# Controller_Keinz_2023.net
KiCad netlist of a schematic drawn in EAGLE
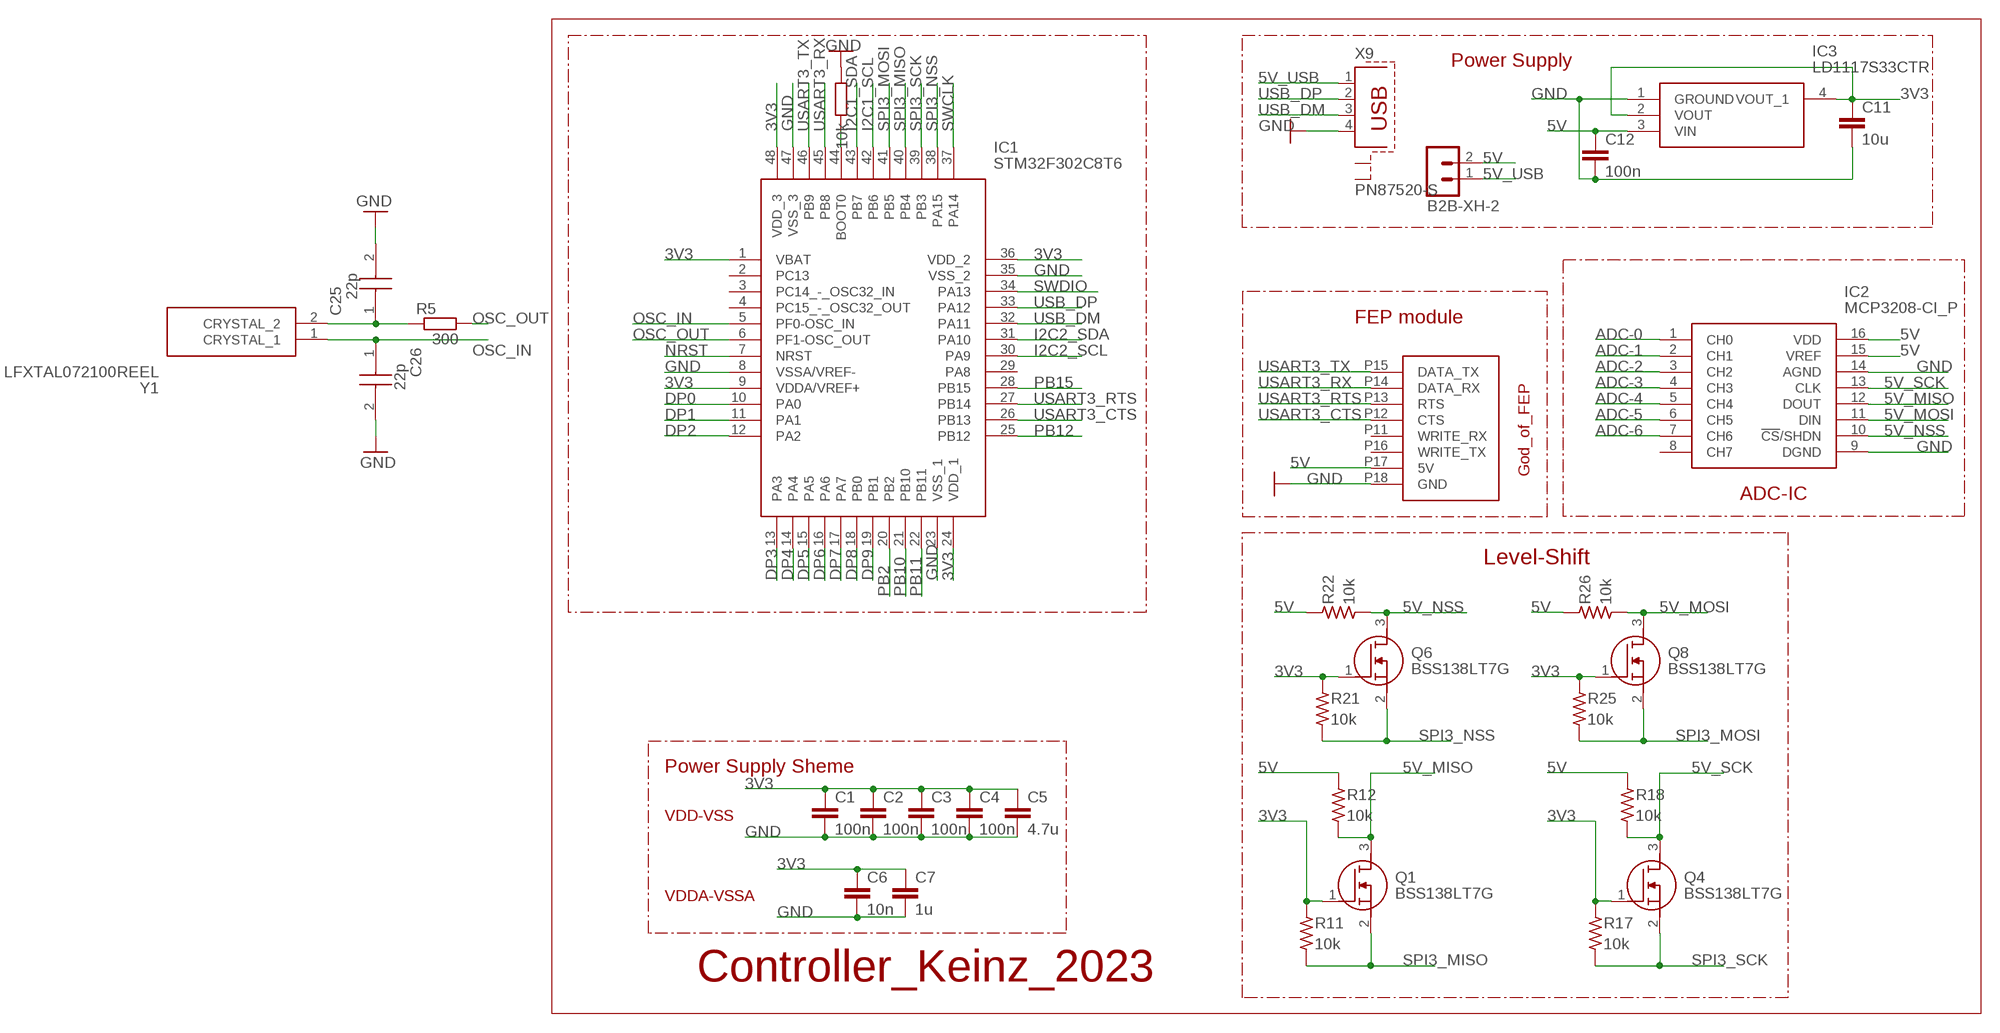
[diagram p0: schematic, sheet 1]
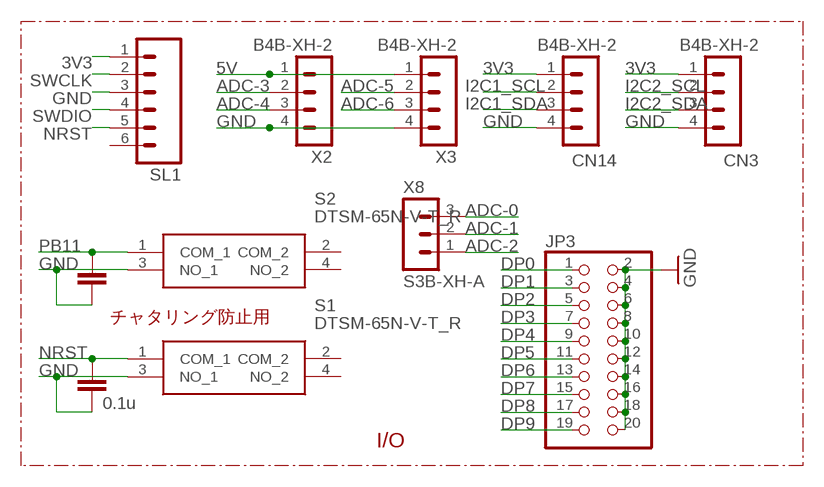
[diagram p1: schematic, sheet 2]
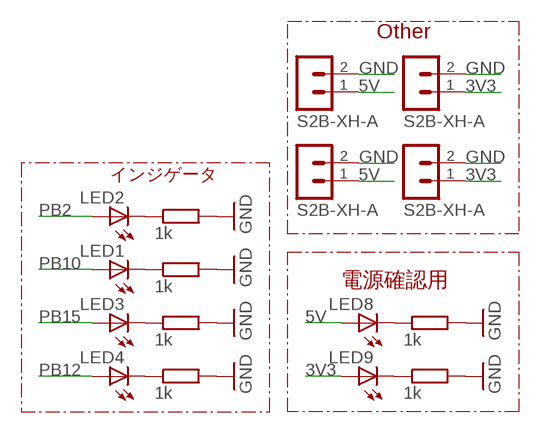
[diagram p2: schematic, sheet 3]

(export (version "E")
  (design (tool "Eeschema 10.0.6"))
  (components
    (comp (ref "LED1")
      (value "LEDCHIP-LED0805")
      (footprint "eagle-import:CHIP-LED0805")
      (libsource (lib "eagle-import") (part "LEDCHIP-LED0805"))
    )
    (comp (ref "LED2")
      (value "LEDCHIP-LED0805")
      (footprint "eagle-import:CHIP-LED0805")
      (libsource (lib "eagle-import") (part "LEDCHIP-LED0805"))
    )
    (comp (ref "LED3")
      (value "LEDCHIP-LED0805")
      (footprint "eagle-import:CHIP-LED0805")
      (libsource (lib "eagle-import") (part "LEDCHIP-LED0805"))
    )
    (comp (ref "LED4")
      (value "LEDCHIP-LED0805")
      (footprint "eagle-import:CHIP-LED0805")
      (libsource (lib "eagle-import") (part "LEDCHIP-LED0805"))
    )
    (comp (ref "LED8")
      (value "LEDCHIP-LED0805")
      (footprint "eagle-import:CHIP-LED0805")
      (libsource (lib "eagle-import") (part "LEDCHIP-LED0805"))
    )
    (comp (ref "LED9")
      (value "LEDCHIP-LED0805")
      (footprint "eagle-import:CHIP-LED0805")
      (libsource (lib "eagle-import") (part "LEDCHIP-LED0805"))
    )
    (comp (ref "R1")
      (value "1k")
      (footprint "eagle-import:R0603")
      (libsource (lib "eagle-import") (part "R-EU_R0603"))
    )
    (comp (ref "R2")
      (value "1k")
      (footprint "eagle-import:R0603")
      (libsource (lib "eagle-import") (part "R-EU_R0603"))
    )
    (comp (ref "R3")
      (value "1k")
      (footprint "eagle-import:R0603")
      (libsource (lib "eagle-import") (part "R-EU_R0603"))
    )
    (comp (ref "R4")
      (value "1k")
      (footprint "eagle-import:R0603")
      (libsource (lib "eagle-import") (part "R-EU_R0603"))
    )
    (comp (ref "R9")
      (value "1k")
      (footprint "eagle-import:R0603")
      (libsource (lib "eagle-import") (part "R-EU_R0603"))
    )
    (comp (ref "R10")
      (value "1k")
      (footprint "eagle-import:R0603")
      (libsource (lib "eagle-import") (part "R-EU_R0603"))
    )
    (comp (ref "X4")
      (value "S2B-XH-A")
      (footprint "eagle-import:S2B-XH-A")
      (libsource (lib "eagle-import") (part "S2B-XH-A"))
    )
    (comp (ref "X5")
      (value "S2B-XH-A")
      (footprint "eagle-import:S2B-XH-A")
      (libsource (lib "eagle-import") (part "S2B-XH-A"))
    )
    (comp (ref "X6")
      (value "S2B-XH-A")
      (footprint "eagle-import:S2B-XH-A")
      (libsource (lib "eagle-import") (part "S2B-XH-A"))
    )
    (comp (ref "X7")
      (value "S2B-XH-A")
      (footprint "eagle-import:S2B-XH-A")
      (libsource (lib "eagle-import") (part "S2B-XH-A"))
    )
    (comp (ref "C1")
      (value "100n")
      (footprint "eagle-import:C0603K")
      (libsource (lib "eagle-import") (part "C-EUC0603K"))
    )
    (comp (ref "C2")
      (value "100n")
      (footprint "eagle-import:C0603K")
      (libsource (lib "eagle-import") (part "C-EUC0603K"))
    )
    (comp (ref "C3")
      (value "100n")
      (footprint "eagle-import:C0603K")
      (libsource (lib "eagle-import") (part "C-EUC0603K"))
    )
    (comp (ref "C4")
      (value "100n")
      (footprint "eagle-import:C0603K")
      (libsource (lib "eagle-import") (part "C-EUC0603K"))
    )
    (comp (ref "C5")
      (value "4.7u")
      (footprint "eagle-import:C0603K")
      (libsource (lib "eagle-import") (part "C-EUC0603K"))
    )
    (comp (ref "C6")
      (value "10n")
      (footprint "eagle-import:C0603K")
      (libsource (lib "eagle-import") (part "C-EUC0603K"))
    )
    (comp (ref "C7")
      (value "1u")
      (footprint "eagle-import:C0603K")
      (libsource (lib "eagle-import") (part "C-EUC0603K"))
    )
    (comp (ref "C11")
      (value "10u")
      (footprint "eagle-import:C0603K")
      (libsource (lib "eagle-import") (part "C-EUC0603K"))
    )
    (comp (ref "C12")
      (value "100n")
      (footprint "eagle-import:C0603K")
      (libsource (lib "eagle-import") (part "C-EUC0603K"))
    )
    (comp (ref "C25")
      (value "22p")
      (footprint "eagle-import:CAPC1709X100N")
      (fields
        (field (name "MANUFACTURER_PART_NUMBER") "AMK107BBJ476MA-RE")
        (field (name "MOUSER_PART_NUMBER") "963-AMK107BBJ476MARE")
        (field (name "RS_PART_NUMBER") "1843762P")
      )
      (libsource (lib "eagle-import") (part "AMK107BBJ476MA-RE"))
    )
    (comp (ref "C26")
      (value "22p")
      (footprint "eagle-import:CAPC1709X100N")
      (fields
        (field (name "MANUFACTURER_PART_NUMBER") "AMK107BBJ476MA-RE")
        (field (name "MOUSER_PART_NUMBER") "963-AMK107BBJ476MARE")
        (field (name "RS_PART_NUMBER") "1843762P")
      )
      (libsource (lib "eagle-import") (part "AMK107BBJ476MA-RE"))
    )
    (comp (ref "FEP_1")
      (value "GOD_OF_FEP")
      (footprint "eagle-import:GOD_OF_FEP")
      (libsource (lib "eagle-import") (part "GOD_OF_FEP"))
    )
    (comp (ref "IC1")
      (value "STM32F302C8T6")
      (footprint "eagle-import:QFP50P900X900X160-48N")
      (fields (field (name "MOUSER_PART_NUMBER") "511-STM32F302C8T6"))
      (libsource (lib "eagle-import") (part "STM32F302C8T6"))
    )
    (comp (ref "IC2")
      (value "MCP3208-CI_P")
      (footprint "eagle-import:DIP781W56P254L1918H533Q16N")
      (fields
        (field (name "ARROW_PART_NUMBER") "MCP3208-CI/P")
        (field (name "MOUSER_PART_NUMBER") "579-MCP3208CIP")
      )
      (libsource (lib "eagle-import") (part "MCP3208-CI_P"))
    )
    (comp (ref "IC3")
      (value "LD1117S33CTR")
      (footprint "eagle-import:SOT230P700X190-4N")
      (fields (field (name "MOUSER_PART_NUMBER") "511-LD1117S33C") (field (name "RS_PART_NUMBER") "6869388P"))
      (libsource (lib "eagle-import") (part "LD1117S33CTR"))
    )
    (comp (ref "Q1")
      (value "BSS138LT7G")
      (footprint "eagle-import:SOT96P237X111-3N")
      (fields (field (name "MOUSER_PART_NUMBER") "863-BSS138LT7G"))
      (libsource (lib "eagle-import") (part "BSS138LT7G"))
    )
    (comp (ref "Q4")
      (value "BSS138LT7G")
      (footprint "eagle-import:SOT96P237X111-3N")
      (fields (field (name "MOUSER_PART_NUMBER") "863-BSS138LT7G"))
      (libsource (lib "eagle-import") (part "BSS138LT7G"))
    )
    (comp (ref "Q6")
      (value "BSS138LT7G")
      (footprint "eagle-import:SOT96P237X111-3N")
      (fields (field (name "MOUSER_PART_NUMBER") "863-BSS138LT7G"))
      (libsource (lib "eagle-import") (part "BSS138LT7G"))
    )
    (comp (ref "Q8")
      (value "BSS138LT7G")
      (footprint "eagle-import:SOT96P237X111-3N")
      (fields (field (name "MOUSER_PART_NUMBER") "863-BSS138LT7G"))
      (libsource (lib "eagle-import") (part "BSS138LT7G"))
    )
    (comp (ref "R5")
      (value "300")
      (footprint "eagle-import:1608")
      (libsource (lib "eagle-import") (part "R1608"))
    )
    (comp (ref "R8")
      (value "10k")
      (footprint "eagle-import:R0603")
      (libsource (lib "eagle-import") (part "R-EU_R0603"))
    )
    (comp (ref "R11")
      (value "10k")
      (footprint "eagle-import:SMD1608")
      (libsource (lib "eagle-import") (part "RESISTOR-US1608"))
    )
    (comp (ref "R12")
      (value "10k")
      (footprint "eagle-import:SMD1608")
      (libsource (lib "eagle-import") (part "RESISTOR-US1608"))
    )
    (comp (ref "R17")
      (value "10k")
      (footprint "eagle-import:SMD1608")
      (libsource (lib "eagle-import") (part "RESISTOR-US1608"))
    )
    (comp (ref "R18")
      (value "10k")
      (footprint "eagle-import:SMD1608")
      (libsource (lib "eagle-import") (part "RESISTOR-US1608"))
    )
    (comp (ref "R21")
      (value "10k")
      (footprint "eagle-import:SMD1608")
      (libsource (lib "eagle-import") (part "RESISTOR-US1608"))
    )
    (comp (ref "R22")
      (value "10k")
      (footprint "eagle-import:SMD1608")
      (libsource (lib "eagle-import") (part "RESISTOR-US1608"))
    )
    (comp (ref "R25")
      (value "10k")
      (footprint "eagle-import:SMD1608")
      (libsource (lib "eagle-import") (part "RESISTOR-US1608"))
    )
    (comp (ref "R26")
      (value "10k")
      (footprint "eagle-import:SMD1608")
      (libsource (lib "eagle-import") (part "RESISTOR-US1608"))
    )
    (comp (ref "X9")
      (value "PN87520-S")
      (footprint "eagle-import:PN87520-S")
      (libsource (lib "eagle-import") (part "PN87520-S"))
    )
    (comp (ref "X22")
      (value "B2B-XH-2")
      (footprint "eagle-import:B2B-XH-A")
      (libsource (lib "eagle-import") (part "B2B-XH-2"))
    )
    (comp (ref "Y1")
      (value "LFXTAL072100REEL")
      (footprint "eagle-import:LFXTAL072100REEL")
      (libsource (lib "eagle-import") (part "LFXTAL072100REEL"))
    )
    (comp (ref "C8")
      (value "0.1u")
      (footprint "eagle-import:C0603K")
      (libsource (lib "eagle-import") (part "C-EUC0603K"))
    )
    (comp (ref "C13")
      (value "0.1u")
      (footprint "eagle-import:C0603K")
      (libsource (lib "eagle-import") (part "C-EUC0603K"))
    )
    (comp (ref "CN3")
      (value "B4B-XH-2")
      (footprint "eagle-import:B4B-XH-A")
      (libsource (lib "eagle-import") (part "B4B-XH-2"))
    )
    (comp (ref "CN14")
      (value "B4B-XH-2")
      (footprint "eagle-import:B4B-XH-A")
      (libsource (lib "eagle-import") (part "B4B-XH-2"))
    )
    (comp (ref "JP3")
      (value "PINHD-2X10")
      (footprint "eagle-import:2X10")
      (libsource (lib "eagle-import") (part "PINHD-2X10"))
    )
    (comp (ref "S1")
      (value "DTSM-65N-V-T_R")
      (footprint "eagle-import:DTSM65NVTR")
      (fields
        (field (name "MANUFACTURER_PART_NUMBER") "DTSM-65N-V-T/R")
        (field (name "MOUSER_PART_NUMBER") "113-DTSM-65N-V-T/R")
      )
      (libsource (lib "eagle-import") (part "DTSM-65N-V-T_R"))
    )
    (comp (ref "S2")
      (value "DTSM-65N-V-T_R")
      (footprint "eagle-import:DTSM65NVTR")
      (fields
        (field (name "MANUFACTURER_PART_NUMBER") "DTSM-65N-V-T/R")
        (field (name "MOUSER_PART_NUMBER") "113-DTSM-65N-V-T/R")
      )
      (libsource (lib "eagle-import") (part "DTSM-65N-V-T_R"))
    )
    (comp (ref "SL1")
      (value "MA06")
      (footprint "eagle-import:06PA")
      (libsource (lib "eagle-import") (part "MA06"))
    )
    (comp (ref "X2")
      (value "B4B-XH-2")
      (footprint "eagle-import:B4B-XH-A")
      (libsource (lib "eagle-import") (part "B4B-XH-2"))
    )
    (comp (ref "X3")
      (value "B4B-XH-2")
      (footprint "eagle-import:B4B-XH-A")
      (libsource (lib "eagle-import") (part "B4B-XH-2"))
    )
    (comp (ref "X8")
      (value "S3B-XH-A")
      (footprint "eagle-import:S3B-XH-A")
      (libsource (lib "eagle-import") (part "S3B-XH-A"))
    )
  )
  (nets
    (net (code "1") (name "3V3") (class "Default")
      (node (ref "C1") (pin "1") (pinfunction "1_1") (pintype "passive"))
      (node (ref "C11") (pin "1") (pinfunction "1_1") (pintype "passive"))
      (node (ref "C2") (pin "1") (pinfunction "1_1") (pintype "passive"))
      (node (ref "C3") (pin "1") (pinfunction "1_1") (pintype "passive"))
      (node (ref "C4") (pin "1") (pinfunction "1_1") (pintype "passive"))
      (node (ref "C5") (pin "1") (pinfunction "1_1") (pintype "passive"))
      (node (ref "C6") (pin "1") (pinfunction "1_1") (pintype "passive"))
      (node (ref "C7") (pin "1") (pinfunction "1_1") (pintype "passive"))
      (node (ref "CN14") (pin "1") (pinfunction "1_1") (pintype "passive"))
      (node (ref "CN3") (pin "1") (pinfunction "1_1") (pintype "passive"))
      (node (ref "IC1") (pin "1") (pinfunction "VBAT_1") (pintype "power_in"))
      (node (ref "IC1") (pin "24") (pinfunction "VDD_1_24") (pintype "power_in"))
      (node (ref "IC1") (pin "36") (pinfunction "VDD_2_36") (pintype "power_in"))
      (node (ref "IC1") (pin "48") (pinfunction "VDD_3_48") (pintype "power_in"))
      (node (ref "IC1") (pin "9") (pinfunction "VDDA/VREF+_9") (pintype "power_in"))
      (node (ref "IC3") (pin "2") (pinfunction "VOUT_2") (pintype "output"))
      (node (ref "IC3") (pin "4") (pinfunction "VOUT_1_4") (pintype "output"))
      (node (ref "LED9") (pin "A") (pinfunction "A_A") (pintype "passive"))
      (node (ref "Q1") (pin "1") (pinfunction "G_1") (pintype "bidirectional"))
      (node (ref "Q4") (pin "1") (pinfunction "G_1") (pintype "bidirectional"))
      (node (ref "Q6") (pin "1") (pinfunction "G_1") (pintype "bidirectional"))
      (node (ref "Q8") (pin "1") (pinfunction "G_1") (pintype "bidirectional"))
      (node (ref "R11") (pin "1") (pinfunction "1_1") (pintype "passive"))
      (node (ref "R17") (pin "1") (pinfunction "1_1") (pintype "passive"))
      (node (ref "R21") (pin "1") (pinfunction "1_1") (pintype "passive"))
      (node (ref "R25") (pin "1") (pinfunction "1_1") (pintype "passive"))
      (node (ref "SL1") (pin "1") (pinfunction "1_1") (pintype "passive"))
      (node (ref "X4") (pin "1") (pinfunction "1_1") (pintype "passive"))
      (node (ref "X5") (pin "1") (pinfunction "1_1") (pintype "passive"))
    )
    (net (code "2") (name "5V") (class "Default")
      (node (ref "C12") (pin "1") (pinfunction "1_1") (pintype "passive"))
      (node (ref "FEP_1") (pin "P17") (pinfunction "5V_P17") (pintype "bidirectional"))
      (node (ref "IC2") (pin "15") (pinfunction "VREF_15") (pintype "bidirectional"))
      (node (ref "IC2") (pin "16") (pinfunction "VDD_16") (pintype "bidirectional"))
      (node (ref "IC3") (pin "3") (pinfunction "VIN_3") (pintype "input"))
      (node (ref "LED8") (pin "A") (pinfunction "A_A") (pintype "passive"))
      (node (ref "R12") (pin "1") (pinfunction "1_1") (pintype "passive"))
      (node (ref "R18") (pin "1") (pinfunction "1_1") (pintype "passive"))
      (node (ref "R22") (pin "1") (pinfunction "1_1") (pintype "passive"))
      (node (ref "R26") (pin "1") (pinfunction "1_1") (pintype "passive"))
      (node (ref "X2") (pin "1") (pinfunction "1_1") (pintype "passive"))
      (node (ref "X22") (pin "2") (pinfunction "2_2") (pintype "passive"))
      (node (ref "X3") (pin "1") (pinfunction "1_1") (pintype "passive"))
      (node (ref "X6") (pin "1") (pinfunction "1_1") (pintype "passive"))
      (node (ref "X7") (pin "1") (pinfunction "1_1") (pintype "passive"))
    )
    (net (code "3") (name "5V_MISO") (class "Default")
      (node (ref "IC2") (pin "12") (pinfunction "DOUT_12") (pintype "bidirectional"))
      (node (ref "Q1") (pin "3") (pinfunction "D_3") (pintype "bidirectional"))
      (node (ref "R12") (pin "2") (pinfunction "2_2") (pintype "passive"))
    )
    (net (code "4") (name "5V_MOSI") (class "Default")
      (node (ref "IC2") (pin "11") (pinfunction "DIN_11") (pintype "bidirectional"))
      (node (ref "Q8") (pin "3") (pinfunction "D_3") (pintype "bidirectional"))
      (node (ref "R26") (pin "2") (pinfunction "2_2") (pintype "passive"))
    )
    (net (code "5") (name "5V_NSS") (class "Default")
      (node (ref "IC2") (pin "10") (pinfunction "~{CS}/SHDN_10") (pintype "bidirectional"))
      (node (ref "Q6") (pin "3") (pinfunction "D_3") (pintype "bidirectional"))
      (node (ref "R22") (pin "2") (pinfunction "2_2") (pintype "passive"))
    )
    (net (code "6") (name "5V_SCK") (class "Default")
      (node (ref "IC2") (pin "13") (pinfunction "CLK_13") (pintype "bidirectional"))
      (node (ref "Q4") (pin "3") (pinfunction "D_3") (pintype "bidirectional"))
      (node (ref "R18") (pin "2") (pinfunction "2_2") (pintype "passive"))
    )
    (net (code "7") (name "5V_USB") (class "Default")
      (node (ref "X22") (pin "1") (pinfunction "1_1") (pintype "passive"))
      (node (ref "X9") (pin "1") (pinfunction "1_1") (pintype "passive"))
    )
    (net (code "8") (name "ADC-0") (class "Default")
      (node (ref "IC2") (pin "1") (pinfunction "CH0_1") (pintype "bidirectional"))
      (node (ref "X8") (pin "3") (pinfunction "3_3") (pintype "passive"))
    )
    (net (code "9") (name "ADC-1") (class "Default")
      (node (ref "IC2") (pin "2") (pinfunction "CH1_2") (pintype "bidirectional"))
      (node (ref "X8") (pin "2") (pinfunction "2_2") (pintype "passive"))
    )
    (net (code "10") (name "ADC-2") (class "Default")
      (node (ref "IC2") (pin "3") (pinfunction "CH2_3") (pintype "bidirectional"))
      (node (ref "X8") (pin "1") (pinfunction "1_1") (pintype "passive"))
    )
    (net (code "11") (name "ADC-3") (class "Default")
      (node (ref "IC2") (pin "4") (pinfunction "CH3_4") (pintype "bidirectional"))
      (node (ref "X2") (pin "2") (pinfunction "2_2") (pintype "passive"))
    )
    (net (code "12") (name "ADC-4") (class "Default")
      (node (ref "IC2") (pin "5") (pinfunction "CH4_5") (pintype "bidirectional"))
      (node (ref "X2") (pin "3") (pinfunction "3_3") (pintype "passive"))
    )
    (net (code "13") (name "ADC-5") (class "Default")
      (node (ref "IC2") (pin "6") (pinfunction "CH5_6") (pintype "bidirectional"))
      (node (ref "X3") (pin "2") (pinfunction "2_2") (pintype "passive"))
    )
    (net (code "14") (name "ADC-6") (class "Default")
      (node (ref "IC2") (pin "7") (pinfunction "CH6_7") (pintype "bidirectional"))
      (node (ref "X3") (pin "3") (pinfunction "3_3") (pintype "passive"))
    )
    (net (code "15") (name "DP0") (class "Default")
      (node (ref "IC1") (pin "10") (pinfunction "PA0_10") (pintype "bidirectional"))
      (node (ref "JP3") (pin "1") (pinfunction "1_1") (pintype "passive"))
    )
    (net (code "16") (name "DP1") (class "Default")
      (node (ref "IC1") (pin "11") (pinfunction "PA1_11") (pintype "bidirectional"))
      (node (ref "JP3") (pin "3") (pinfunction "3_3") (pintype "passive"))
    )
    (net (code "17") (name "DP2") (class "Default")
      (node (ref "IC1") (pin "12") (pinfunction "PA2_12") (pintype "bidirectional"))
      (node (ref "JP3") (pin "5") (pinfunction "5_5") (pintype "passive"))
    )
    (net (code "18") (name "DP3") (class "Default")
      (node (ref "IC1") (pin "13") (pinfunction "PA3_13") (pintype "bidirectional"))
      (node (ref "JP3") (pin "7") (pinfunction "7_7") (pintype "passive"))
    )
    (net (code "19") (name "DP4") (class "Default")
      (node (ref "IC1") (pin "14") (pinfunction "PA4_14") (pintype "bidirectional"))
      (node (ref "JP3") (pin "9") (pinfunction "9_9") (pintype "passive"))
    )
    (net (code "20") (name "DP5") (class "Default")
      (node (ref "IC1") (pin "15") (pinfunction "PA5_15") (pintype "bidirectional"))
      (node (ref "JP3") (pin "11") (pinfunction "11_11") (pintype "passive"))
    )
    (net (code "21") (name "DP6") (class "Default")
      (node (ref "IC1") (pin "16") (pinfunction "PA6_16") (pintype "bidirectional"))
      (node (ref "JP3") (pin "13") (pinfunction "13_13") (pintype "passive"))
    )
    (net (code "22") (name "DP7") (class "Default")
      (node (ref "IC1") (pin "17") (pinfunction "PA7_17") (pintype "bidirectional"))
      (node (ref "JP3") (pin "15") (pinfunction "15_15") (pintype "passive"))
    )
    (net (code "23") (name "DP8") (class "Default")
      (node (ref "IC1") (pin "18") (pinfunction "PB0_18") (pintype "bidirectional"))
      (node (ref "JP3") (pin "17") (pinfunction "17_17") (pintype "passive"))
    )
    (net (code "24") (name "DP9") (class "Default")
      (node (ref "IC1") (pin "19") (pinfunction "PB1_19") (pintype "bidirectional"))
      (node (ref "JP3") (pin "19") (pinfunction "19_19") (pintype "passive"))
    )
    (net (code "25") (name "GND") (class "Default")
      (node (ref "C1") (pin "2") (pinfunction "2_2") (pintype "passive"))
      (node (ref "C11") (pin "2") (pinfunction "2_2") (pintype "passive"))
      (node (ref "C12") (pin "2") (pinfunction "2_2") (pintype "passive"))
      (node (ref "C13") (pin "2") (pinfunction "2_2") (pintype "passive"))
      (node (ref "C2") (pin "2") (pinfunction "2_2") (pintype "passive"))
      (node (ref "C25") (pin "2") (pinfunction "2_2") (pintype "bidirectional"))
      (node (ref "C26") (pin "2") (pinfunction "2_2") (pintype "bidirectional"))
      (node (ref "C3") (pin "2") (pinfunction "2_2") (pintype "passive"))
      (node (ref "C4") (pin "2") (pinfunction "2_2") (pintype "passive"))
      (node (ref "C5") (pin "2") (pinfunction "2_2") (pintype "passive"))
      (node (ref "C6") (pin "2") (pinfunction "2_2") (pintype "passive"))
      (node (ref "C7") (pin "2") (pinfunction "2_2") (pintype "passive"))
      (node (ref "C8") (pin "2") (pinfunction "2_2") (pintype "passive"))
      (node (ref "CN14") (pin "4") (pinfunction "4_4") (pintype "passive"))
      (node (ref "CN3") (pin "4") (pinfunction "4_4") (pintype "passive"))
      (node (ref "FEP_1") (pin "P18") (pinfunction "GND_P18") (pintype "bidirectional"))
      (node (ref "IC1") (pin "23") (pinfunction "VSS_1_23") (pintype "power_in"))
      (node (ref "IC1") (pin "35") (pinfunction "VSS_2_35") (pintype "power_in"))
      (node (ref "IC1") (pin "47") (pinfunction "VSS_3_47") (pintype "power_in"))
      (node (ref "IC1") (pin "8") (pinfunction "VSSA/VREF-_8") (pintype "power_in"))
      (node (ref "IC2") (pin "14") (pinfunction "AGND_14") (pintype "bidirectional"))
      (node (ref "IC2") (pin "9") (pinfunction "DGND_9") (pintype "bidirectional"))
      (node (ref "IC3") (pin "1") (pinfunction "GROUND_1") (pintype "bidirectional"))
      (node (ref "JP3") (pin "10") (pinfunction "10_10") (pintype "passive"))
      (node (ref "JP3") (pin "12") (pinfunction "12_12") (pintype "passive"))
      (node (ref "JP3") (pin "14") (pinfunction "14_14") (pintype "passive"))
      (node (ref "JP3") (pin "16") (pinfunction "16_16") (pintype "passive"))
      (node (ref "JP3") (pin "18") (pinfunction "18_18") (pintype "passive"))
      (node (ref "JP3") (pin "2") (pinfunction "2_2") (pintype "passive"))
      (node (ref "JP3") (pin "20") (pinfunction "20_20") (pintype "passive"))
      (node (ref "JP3") (pin "4") (pinfunction "4_4") (pintype "passive"))
      (node (ref "JP3") (pin "6") (pinfunction "6_6") (pintype "passive"))
      (node (ref "JP3") (pin "8") (pinfunction "8_8") (pintype "passive"))
      (node (ref "R1") (pin "2") (pinfunction "2_2") (pintype "passive"))
      (node (ref "R10") (pin "2") (pinfunction "2_2") (pintype "passive"))
      (node (ref "R2") (pin "2") (pinfunction "2_2") (pintype "passive"))
      (node (ref "R3") (pin "2") (pinfunction "2_2") (pintype "passive"))
      (node (ref "R4") (pin "2") (pinfunction "2_2") (pintype "passive"))
      (node (ref "R8") (pin "1") (pinfunction "1_1") (pintype "passive"))
      (node (ref "R9") (pin "2") (pinfunction "2_2") (pintype "passive"))
      (node (ref "S1") (pin "3") (pinfunction "NO_1_3") (pintype "bidirectional"))
      (node (ref "S2") (pin "3") (pinfunction "NO_1_3") (pintype "bidirectional"))
      (node (ref "SL1") (pin "3") (pinfunction "3_3") (pintype "passive"))
      (node (ref "X2") (pin "4") (pinfunction "4_4") (pintype "passive"))
      (node (ref "X3") (pin "4") (pinfunction "4_4") (pintype "passive"))
      (node (ref "X4") (pin "2") (pinfunction "2_2") (pintype "passive"))
      (node (ref "X5") (pin "2") (pinfunction "2_2") (pintype "passive"))
      (node (ref "X6") (pin "2") (pinfunction "2_2") (pintype "passive"))
      (node (ref "X7") (pin "2") (pinfunction "2_2") (pintype "passive"))
      (node (ref "X9") (pin "4") (pinfunction "4_4") (pintype "passive"))
    )
    (net (code "26") (name "I2C1_SCL") (class "Default")
      (node (ref "CN14") (pin "2") (pinfunction "2_2") (pintype "passive"))
      (node (ref "IC1") (pin "42") (pinfunction "PB6_42") (pintype "bidirectional"))
    )
    (net (code "27") (name "I2C1_SDA") (class "Default")
      (node (ref "CN14") (pin "3") (pinfunction "3_3") (pintype "passive"))
      (node (ref "IC1") (pin "43") (pinfunction "PB7_43") (pintype "bidirectional"))
    )
    (net (code "28") (name "I2C2_SCL") (class "Default")
      (node (ref "CN3") (pin "2") (pinfunction "2_2") (pintype "passive"))
      (node (ref "IC1") (pin "30") (pinfunction "PA9_30") (pintype "bidirectional"))
    )
    (net (code "29") (name "I2C2_SDA") (class "Default")
      (node (ref "CN3") (pin "3") (pinfunction "3_3") (pintype "passive"))
      (node (ref "IC1") (pin "31") (pinfunction "PA10_31") (pintype "bidirectional"))
    )
    (net (code "30") (name "NRST") (class "Default")
      (node (ref "C13") (pin "1") (pinfunction "1_1") (pintype "passive"))
      (node (ref "IC1") (pin "7") (pinfunction "NRST_7") (pintype "bidirectional"))
      (node (ref "S1") (pin "1") (pinfunction "COM_1_1") (pintype "bidirectional"))
      (node (ref "SL1") (pin "5") (pinfunction "5_5") (pintype "passive"))
    )
    (net (code "31") (name "Net-(IC1-BOOT0)") (class "Default")
      (node (ref "IC1") (pin "44") (pinfunction "BOOT0_44") (pintype "bidirectional"))
      (node (ref "R8") (pin "2") (pinfunction "2_2") (pintype "passive"))
    )
    (net (code "32") (name "Net-(LED1-PadC)") (class "Default")
      (node (ref "LED1") (pin "C") (pinfunction "C_C") (pintype "passive"))
      (node (ref "R2") (pin "1") (pinfunction "1_1") (pintype "passive"))
    )
    (net (code "33") (name "Net-(LED2-PadC)") (class "Default")
      (node (ref "LED2") (pin "C") (pinfunction "C_C") (pintype "passive"))
      (node (ref "R1") (pin "1") (pinfunction "1_1") (pintype "passive"))
    )
    (net (code "34") (name "Net-(LED3-PadC)") (class "Default")
      (node (ref "LED3") (pin "C") (pinfunction "C_C") (pintype "passive"))
      (node (ref "R3") (pin "1") (pinfunction "1_1") (pintype "passive"))
    )
    (net (code "35") (name "Net-(LED4-PadC)") (class "Default")
      (node (ref "LED4") (pin "C") (pinfunction "C_C") (pintype "passive"))
      (node (ref "R4") (pin "1") (pinfunction "1_1") (pintype "passive"))
    )
    (net (code "36") (name "Net-(LED8-PadC)") (class "Default")
      (node (ref "LED8") (pin "C") (pinfunction "C_C") (pintype "passive"))
      (node (ref "R9") (pin "1") (pinfunction "1_1") (pintype "passive"))
    )
    (net (code "37") (name "Net-(LED9-PadC)") (class "Default")
      (node (ref "LED9") (pin "C") (pinfunction "C_C") (pintype "passive"))
      (node (ref "R10") (pin "1") (pinfunction "1_1") (pintype "passive"))
    )
    (net (code "38") (name "Net-(Y1-CRYSTAL_2)") (class "Default")
      (node (ref "C25") (pin "1") (pinfunction "1_1") (pintype "bidirectional"))
      (node (ref "R5") (pin "1") (pinfunction "1_1") (pintype "passive"))
      (node (ref "Y1") (pin "2") (pinfunction "CRYSTAL_2_2") (pintype "bidirectional"))
    )
    (net (code "39") (name "OSC_IN") (class "Default")
      (node (ref "C26") (pin "1") (pinfunction "1_1") (pintype "bidirectional"))
      (node (ref "IC1") (pin "5") (pinfunction "PF0-OSC_IN_5") (pintype "bidirectional"))
      (node (ref "Y1") (pin "1") (pinfunction "CRYSTAL_1_1") (pintype "bidirectional"))
    )
    (net (code "40") (name "OSC_OUT") (class "Default")
      (node (ref "IC1") (pin "6") (pinfunction "PF1-OSC_OUT_6") (pintype "bidirectional"))
      (node (ref "R5") (pin "2") (pinfunction "2_2") (pintype "passive"))
    )
    (net (code "41") (name "PB2") (class "Default")
      (node (ref "IC1") (pin "20") (pinfunction "PB2_20") (pintype "bidirectional"))
      (node (ref "LED2") (pin "A") (pinfunction "A_A") (pintype "passive"))
    )
    (net (code "42") (name "PB10") (class "Default")
      (node (ref "IC1") (pin "21") (pinfunction "PB10_21") (pintype "bidirectional"))
      (node (ref "LED1") (pin "A") (pinfunction "A_A") (pintype "passive"))
    )
    (net (code "43") (name "PB11") (class "Default")
      (node (ref "C8") (pin "1") (pinfunction "1_1") (pintype "passive"))
      (node (ref "IC1") (pin "22") (pinfunction "PB11_22") (pintype "bidirectional"))
      (node (ref "S2") (pin "1") (pinfunction "COM_1_1") (pintype "bidirectional"))
    )
    (net (code "44") (name "PB12") (class "Default")
      (node (ref "IC1") (pin "25") (pinfunction "PB12_25") (pintype "bidirectional"))
      (node (ref "LED4") (pin "A") (pinfunction "A_A") (pintype "passive"))
    )
    (net (code "45") (name "PB15") (class "Default")
      (node (ref "IC1") (pin "28") (pinfunction "PB15_28") (pintype "bidirectional"))
      (node (ref "LED3") (pin "A") (pinfunction "A_A") (pintype "passive"))
    )
    (net (code "46") (name "SPI3_MISO") (class "Default")
      (node (ref "IC1") (pin "40") (pinfunction "PB4_40") (pintype "bidirectional"))
      (node (ref "Q1") (pin "2") (pinfunction "S_2") (pintype "bidirectional"))
      (node (ref "R11") (pin "2") (pinfunction "2_2") (pintype "passive"))
    )
    (net (code "47") (name "SPI3_MOSI") (class "Default")
      (node (ref "IC1") (pin "41") (pinfunction "PB5_41") (pintype "bidirectional"))
      (node (ref "Q8") (pin "2") (pinfunction "S_2") (pintype "bidirectional"))
      (node (ref "R25") (pin "2") (pinfunction "2_2") (pintype "passive"))
    )
    (net (code "48") (name "SPI3_NSS") (class "Default")
      (node (ref "IC1") (pin "38") (pinfunction "PA15_38") (pintype "bidirectional"))
      (node (ref "Q6") (pin "2") (pinfunction "S_2") (pintype "bidirectional"))
      (node (ref "R21") (pin "2") (pinfunction "2_2") (pintype "passive"))
    )
    (net (code "49") (name "SPI3_SCK") (class "Default")
      (node (ref "IC1") (pin "39") (pinfunction "PB3_39") (pintype "bidirectional"))
      (node (ref "Q4") (pin "2") (pinfunction "S_2") (pintype "bidirectional"))
      (node (ref "R17") (pin "2") (pinfunction "2_2") (pintype "passive"))
    )
    (net (code "50") (name "SWCLK") (class "Default")
      (node (ref "IC1") (pin "37") (pinfunction "PA14_37") (pintype "bidirectional"))
      (node (ref "SL1") (pin "2") (pinfunction "2_2") (pintype "passive"))
    )
    (net (code "51") (name "SWDIO") (class "Default")
      (node (ref "IC1") (pin "34") (pinfunction "PA13_34") (pintype "bidirectional"))
      (node (ref "SL1") (pin "4") (pinfunction "4_4") (pintype "passive"))
    )
    (net (code "52") (name "USART3_CTS") (class "Default")
      (node (ref "FEP_1") (pin "P12") (pinfunction "CTS_P12") (pintype "bidirectional"))
      (node (ref "IC1") (pin "26") (pinfunction "PB13_26") (pintype "bidirectional"))
    )
    (net (code "53") (name "USART3_RTS") (class "Default")
      (node (ref "FEP_1") (pin "P13") (pinfunction "RTS_P13") (pintype "bidirectional"))
      (node (ref "IC1") (pin "27") (pinfunction "PB14_27") (pintype "bidirectional"))
    )
    (net (code "54") (name "USART3_RX") (class "Default")
      (node (ref "FEP_1") (pin "P14") (pinfunction "DATA_RX_P14") (pintype "bidirectional"))
      (node (ref "IC1") (pin "45") (pinfunction "PB8_45") (pintype "bidirectional"))
    )
    (net (code "55") (name "USART3_TX") (class "Default")
      (node (ref "FEP_1") (pin "P15") (pinfunction "DATA_TX_P15") (pintype "bidirectional"))
      (node (ref "IC1") (pin "46") (pinfunction "PB9_46") (pintype "bidirectional"))
    )
    (net (code "56") (name "USB_DM") (class "Default")
      (node (ref "IC1") (pin "32") (pinfunction "PA11_32") (pintype "bidirectional"))
      (node (ref "X9") (pin "3") (pinfunction "3_3") (pintype "passive"))
    )
    (net (code "57") (name "USB_DP") (class "Default")
      (node (ref "IC1") (pin "33") (pinfunction "PA12_33") (pintype "bidirectional"))
      (node (ref "X9") (pin "2") (pinfunction "2_2") (pintype "passive"))
    )
    (net (code "58") (name "unconnected-(FEP_1-WRITE_RX-PadP11)") (class "Default")
      (node (ref "FEP_1") (pin "P11") (pinfunction "WRITE_RX_P11") (pintype "bidirectional"))
    )
    (net (code "59") (name "unconnected-(FEP_1-WRITE_TX-PadP16)") (class "Default")
      (node (ref "FEP_1") (pin "P16") (pinfunction "WRITE_TX_P16") (pintype "bidirectional"))
    )
    (net (code "60") (name "unconnected-(IC1-PA8-Pad29)") (class "Default")
      (node (ref "IC1") (pin "29") (pinfunction "PA8_29") (pintype "bidirectional"))
    )
    (net (code "61") (name "unconnected-(IC1-PC13-Pad2)") (class "Default")
      (node (ref "IC1") (pin "2") (pinfunction "PC13_2") (pintype "bidirectional"))
    )
    (net (code "62") (name "unconnected-(IC1-PC14_-_OSC32_IN-Pad3)") (class "Default")
      (node (ref "IC1") (pin "3") (pinfunction "PC14_-_OSC32_IN_3") (pintype "bidirectional"))
    )
    (net (code "63") (name "unconnected-(IC1-PC15_-_OSC32_OUT-Pad4)") (class "Default")
      (node (ref "IC1") (pin "4") (pinfunction "PC15_-_OSC32_OUT_4") (pintype "bidirectional"))
    )
    (net (code "64") (name "unconnected-(IC2-CH7-Pad8)") (class "Default")
      (node (ref "IC2") (pin "8") (pinfunction "CH7_8") (pintype "bidirectional"))
    )
    (net (code "65") (name "unconnected-(S1-COM_2-Pad2)") (class "Default")
      (node (ref "S1") (pin "2") (pinfunction "COM_2_2") (pintype "bidirectional"))
    )
    (net (code "66") (name "unconnected-(S1-NO_2-Pad4)") (class "Default")
      (node (ref "S1") (pin "4") (pinfunction "NO_2_4") (pintype "bidirectional"))
    )
    (net (code "67") (name "unconnected-(S2-COM_2-Pad2)") (class "Default")
      (node (ref "S2") (pin "2") (pinfunction "COM_2_2") (pintype "bidirectional"))
    )
    (net (code "68") (name "unconnected-(S2-NO_2-Pad4)") (class "Default")
      (node (ref "S2") (pin "4") (pinfunction "NO_2_4") (pintype "bidirectional"))
    )
    (net (code "69") (name "unconnected-(SL1-Pad6)") (class "Default")
      (node (ref "SL1") (pin "6") (pinfunction "6_6") (pintype "passive"))
    )
    (net (code "70") (name "unconnected-(X9-PadS1)") (class "Default")
      (node (ref "X9") (pin "S1") (pinfunction "S1_S1") (pintype "passive"))
    )
    (net (code "71") (name "unconnected-(X9-PadS2)") (class "Default")
      (node (ref "X9") (pin "S2") (pinfunction "S2_S2") (pintype "passive"))
    )
  )
)
